# BMS_breakout.net
KiCad netlist of a schematic drawn in EAGLE
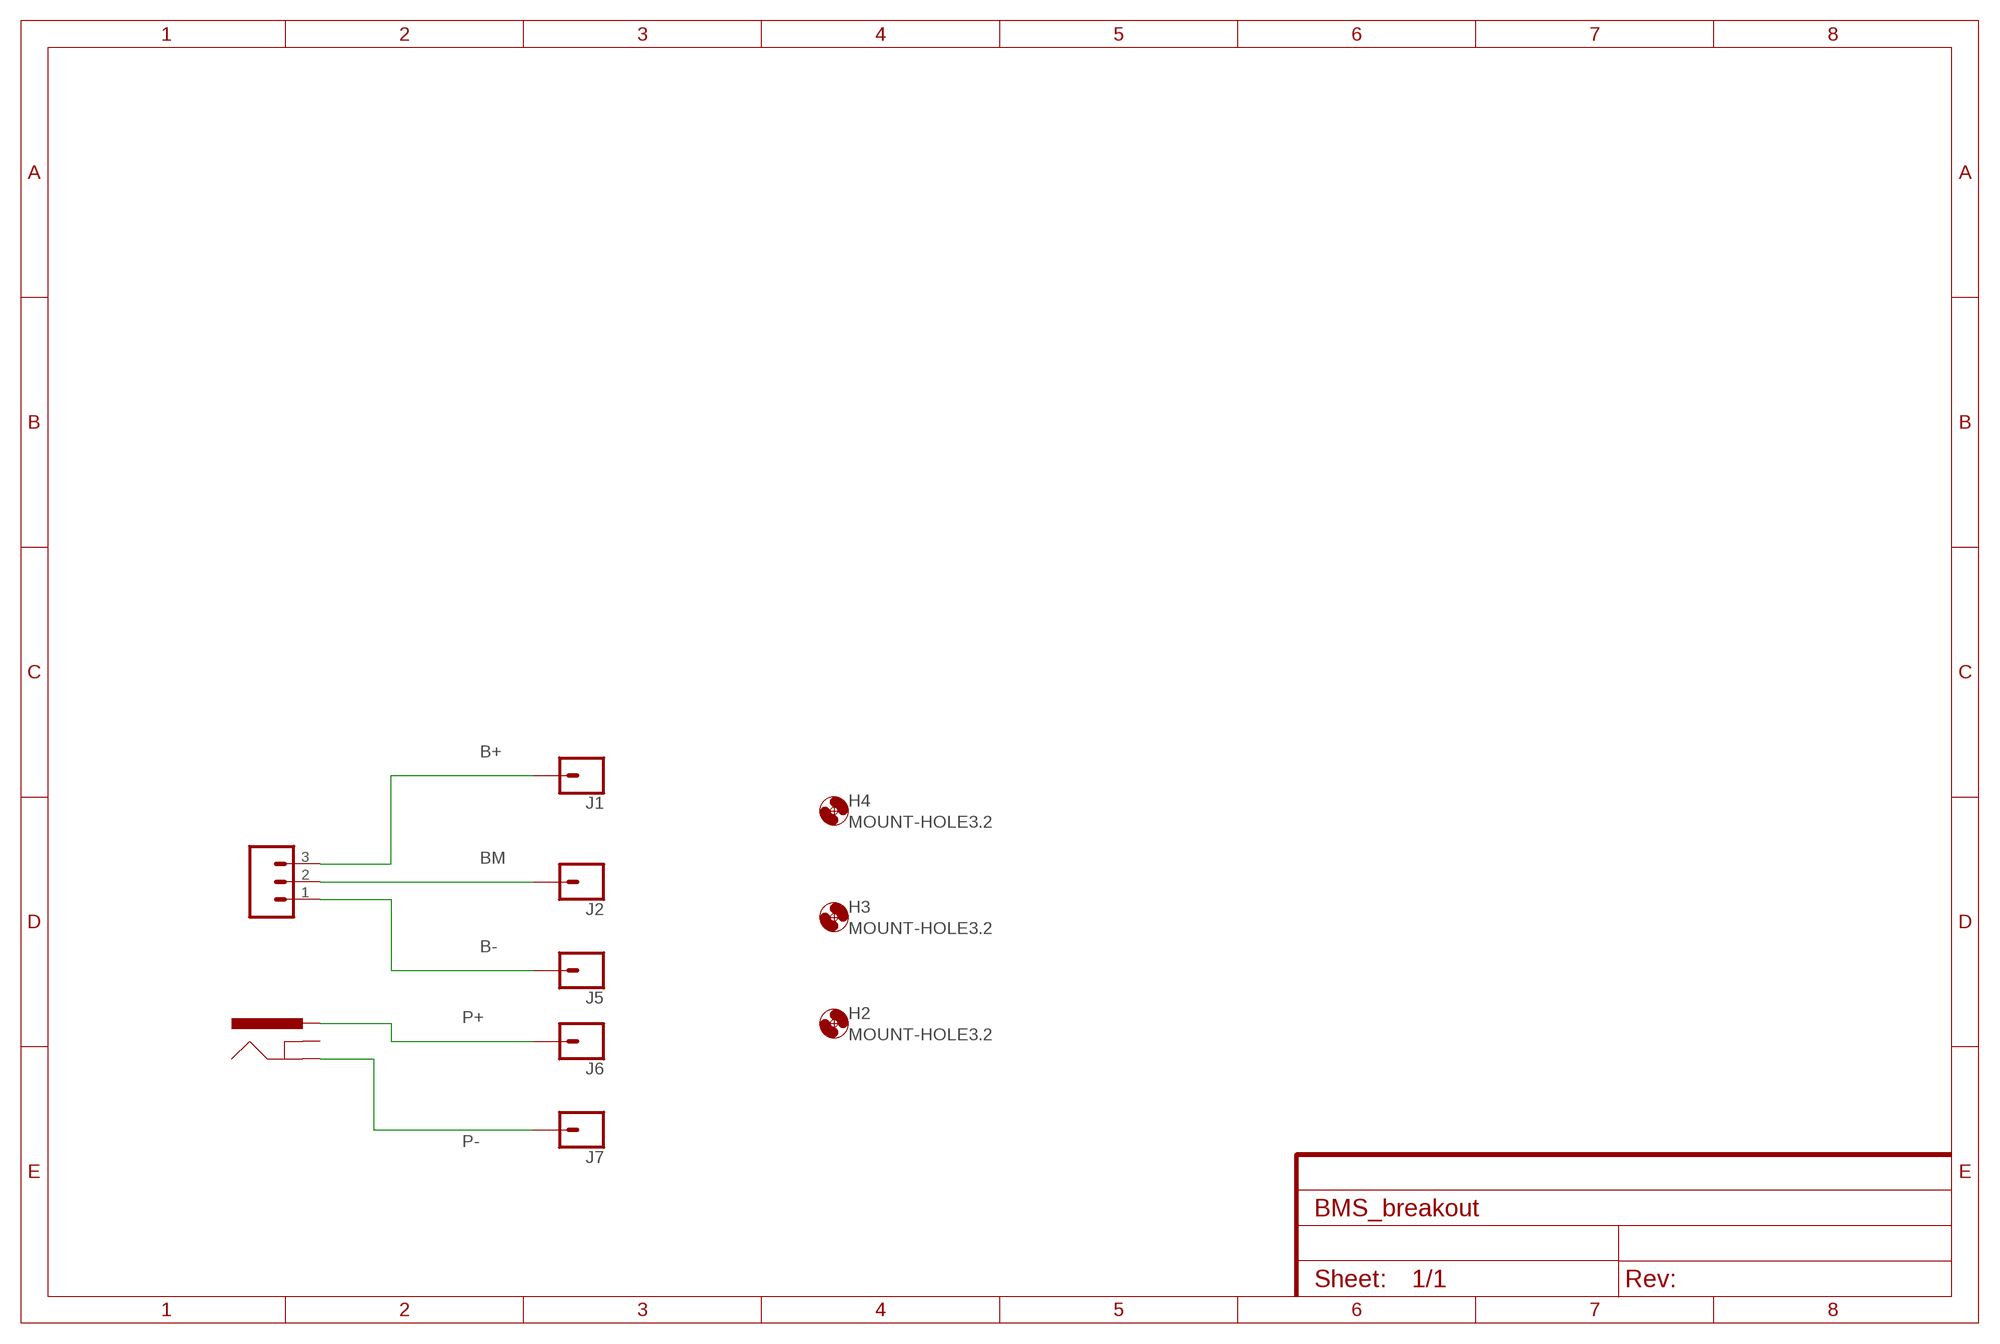
[diagram p0: schematic, sheet 1]

(export (version "E")
  (design (tool "Eeschema 10.0.6"))
  (components
    (comp (ref "H2")
      (value "MOUNT-HOLE3.2")
      (footprint "eagle-import:3,2")
      (libsource (lib "eagle-import") (part "MOUNT-HOLE3.2"))
    )
    (comp (ref "H3")
      (value "MOUNT-HOLE3.2")
      (footprint "eagle-import:3,2")
      (libsource (lib "eagle-import") (part "MOUNT-HOLE3.2"))
    )
    (comp (ref "H4")
      (value "MOUNT-HOLE3.2")
      (footprint "eagle-import:3,2")
      (libsource (lib "eagle-import") (part "MOUNT-HOLE3.2"))
    )
    (comp (ref "J1")
      (value "CONN_01")
      (footprint "eagle-import:1X01")
      (libsource (lib "eagle-import") (part "CONN_01"))
    )
    (comp (ref "J2")
      (value "CONN_01")
      (footprint "eagle-import:1X01")
      (libsource (lib "eagle-import") (part "CONN_01"))
    )
    (comp (ref "J3")
      (value "CONN_03-SCREW-5MM")
      (footprint "eagle-import:SCREWTERMINAL-5MM-3")
      (libsource (lib "eagle-import") (part "CONN_03-SCREW-5MM"))
    )
    (comp (ref "J4")
      (value "POWER_JACKPTH_BREAD")
      (footprint "eagle-import:POWER_JACK_PTH_BREAD")
      (libsource (lib "eagle-import") (part "POWER_JACKPTH_BREAD"))
    )
    (comp (ref "J5")
      (value "CONN_01")
      (footprint "eagle-import:1X01")
      (libsource (lib "eagle-import") (part "CONN_01"))
    )
    (comp (ref "J6")
      (value "CONN_01")
      (footprint "eagle-import:1X01")
      (libsource (lib "eagle-import") (part "CONN_01"))
    )
    (comp (ref "J7")
      (value "CONN_01")
      (footprint "eagle-import:1X01")
      (libsource (lib "eagle-import") (part "CONN_01"))
    )
  )
  (nets
    (net (code "1") (name "/B+") (class "Default")
      (node (ref "J1") (pin "1") (pinfunction "1_1") (pintype "passive"))
      (node (ref "J3") (pin "3") (pinfunction "3_3") (pintype "passive"))
    )
    (net (code "2") (name "/B-") (class "Default")
      (node (ref "J3") (pin "1") (pinfunction "1_1") (pintype "passive"))
      (node (ref "J5") (pin "1") (pinfunction "1_1") (pintype "passive"))
    )
    (net (code "3") (name "/BM") (class "Default")
      (node (ref "J2") (pin "1") (pinfunction "1_1") (pintype "passive"))
      (node (ref "J3") (pin "2") (pinfunction "2_2") (pintype "passive"))
    )
    (net (code "4") (name "/P+") (class "Default")
      (node (ref "J4") (pin "PWR") (pinfunction "PWR_PWR") (pintype "bidirectional"))
      (node (ref "J6") (pin "1") (pinfunction "1_1") (pintype "passive"))
    )
    (net (code "5") (name "/P-") (class "Default")
      (node (ref "J4") (pin "GND") (pinfunction "GND_GND") (pintype "bidirectional"))
      (node (ref "J7") (pin "1") (pinfunction "1_1") (pintype "passive"))
    )
    (net (code "6") (name "unconnected-(J4-PadGNDBREAK)") (class "Default")
      (node (ref "J4") (pin "GNDBREAK") (pinfunction "GNDBREAK_GNDBREAK") (pintype "bidirectional"))
    )
  )
)
